# trrs-mitm.net
KiCad netlist of a schematic drawn in EAGLE
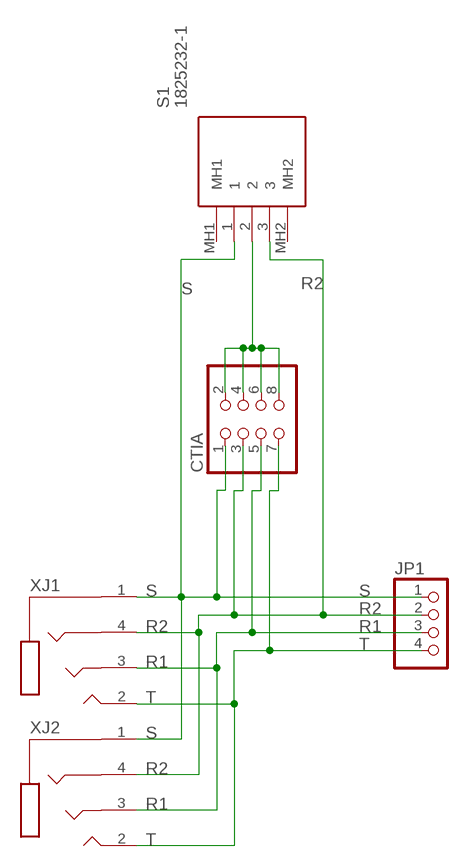
[diagram p0: schematic, sheet 1]

(export (version "E")
  (design (tool "Eeschema 10.0.6"))
  (components
    (comp (ref "CTIA")
      (value "PINHD-2X4/90")
      (footprint "eagle-import:2X04_90")
      (libsource (lib "eagle-import") (part "PINHD-2X4/90"))
    )
    (comp (ref "JP1")
      (value "PINHD-1X4")
      (footprint "eagle-import:1X04")
      (libsource (lib "eagle-import") (part "PINHD-1X4"))
    )
    (comp (ref "S1")
      (value "1825232-1")
      (footprint "eagle-import:18252321")
      (fields (field (name "MOUSER_PART_NUMBER") "655-1825232-1"))
      (libsource (lib "eagle-import") (part "1825232-1"))
    )
    (comp (ref "XJ1")
      (value "ASJ171B")
      (footprint "eagle-import:ASJ171B")
      (libsource (lib "eagle-import") (part "ASJ171B"))
    )
    (comp (ref "XJ2")
      (value "ASJ171B")
      (footprint "eagle-import:ASJ171B")
      (libsource (lib "eagle-import") (part "ASJ171B"))
    )
  )
  (nets
    (net (code "1") (name "/R1") (class "Default")
      (node (ref "CTIA") (pin "5") (pinfunction "5_5") (pintype "passive"))
      (node (ref "JP1") (pin "3") (pinfunction "3_3") (pintype "passive"))
      (node (ref "XJ1") (pin "3") (pinfunction "3_3") (pintype "passive"))
      (node (ref "XJ2") (pin "3") (pinfunction "3_3") (pintype "passive"))
    )
    (net (code "2") (name "/R2") (class "Default")
      (node (ref "CTIA") (pin "3") (pinfunction "3_3") (pintype "passive"))
      (node (ref "JP1") (pin "2") (pinfunction "2_2") (pintype "passive"))
      (node (ref "S1") (pin "3") (pinfunction "3_3") (pintype "bidirectional"))
      (node (ref "XJ1") (pin "4") (pinfunction "4_4") (pintype "passive"))
      (node (ref "XJ2") (pin "4") (pinfunction "4_4") (pintype "passive"))
    )
    (net (code "3") (name "/S") (class "Default")
      (node (ref "CTIA") (pin "1") (pinfunction "1_1") (pintype "passive"))
      (node (ref "JP1") (pin "1") (pinfunction "1_1") (pintype "passive"))
      (node (ref "S1") (pin "1") (pinfunction "1_1") (pintype "bidirectional"))
      (node (ref "XJ1") (pin "1") (pinfunction "1_1") (pintype "passive"))
      (node (ref "XJ2") (pin "1") (pinfunction "1_1") (pintype "passive"))
    )
    (net (code "4") (name "/T") (class "Default")
      (node (ref "CTIA") (pin "7") (pinfunction "7_7") (pintype "passive"))
      (node (ref "JP1") (pin "4") (pinfunction "4_4") (pintype "passive"))
      (node (ref "XJ1") (pin "2") (pinfunction "2_2") (pintype "passive"))
      (node (ref "XJ2") (pin "2") (pinfunction "2_2") (pintype "passive"))
    )
    (net (code "5") (name "Net-(CTIA-Pad2)") (class "Default")
      (node (ref "CTIA") (pin "2") (pinfunction "2_2") (pintype "passive"))
      (node (ref "CTIA") (pin "4") (pinfunction "4_4") (pintype "passive"))
      (node (ref "CTIA") (pin "6") (pinfunction "6_6") (pintype "passive"))
      (node (ref "CTIA") (pin "8") (pinfunction "8_8") (pintype "passive"))
      (node (ref "S1") (pin "2") (pinfunction "2_2") (pintype "bidirectional"))
    )
    (net (code "6") (name "unconnected-(S1-PadMH1)") (class "Default")
      (node (ref "S1") (pin "MH1") (pinfunction "MH1_MH1") (pintype "bidirectional"))
    )
    (net (code "7") (name "unconnected-(S1-PadMH2)") (class "Default")
      (node (ref "S1") (pin "MH2") (pinfunction "MH2_MH2") (pintype "bidirectional"))
    )
  )
)
